# ece4416-project-v2.net
KiCad netlist of a schematic drawn in EAGLE
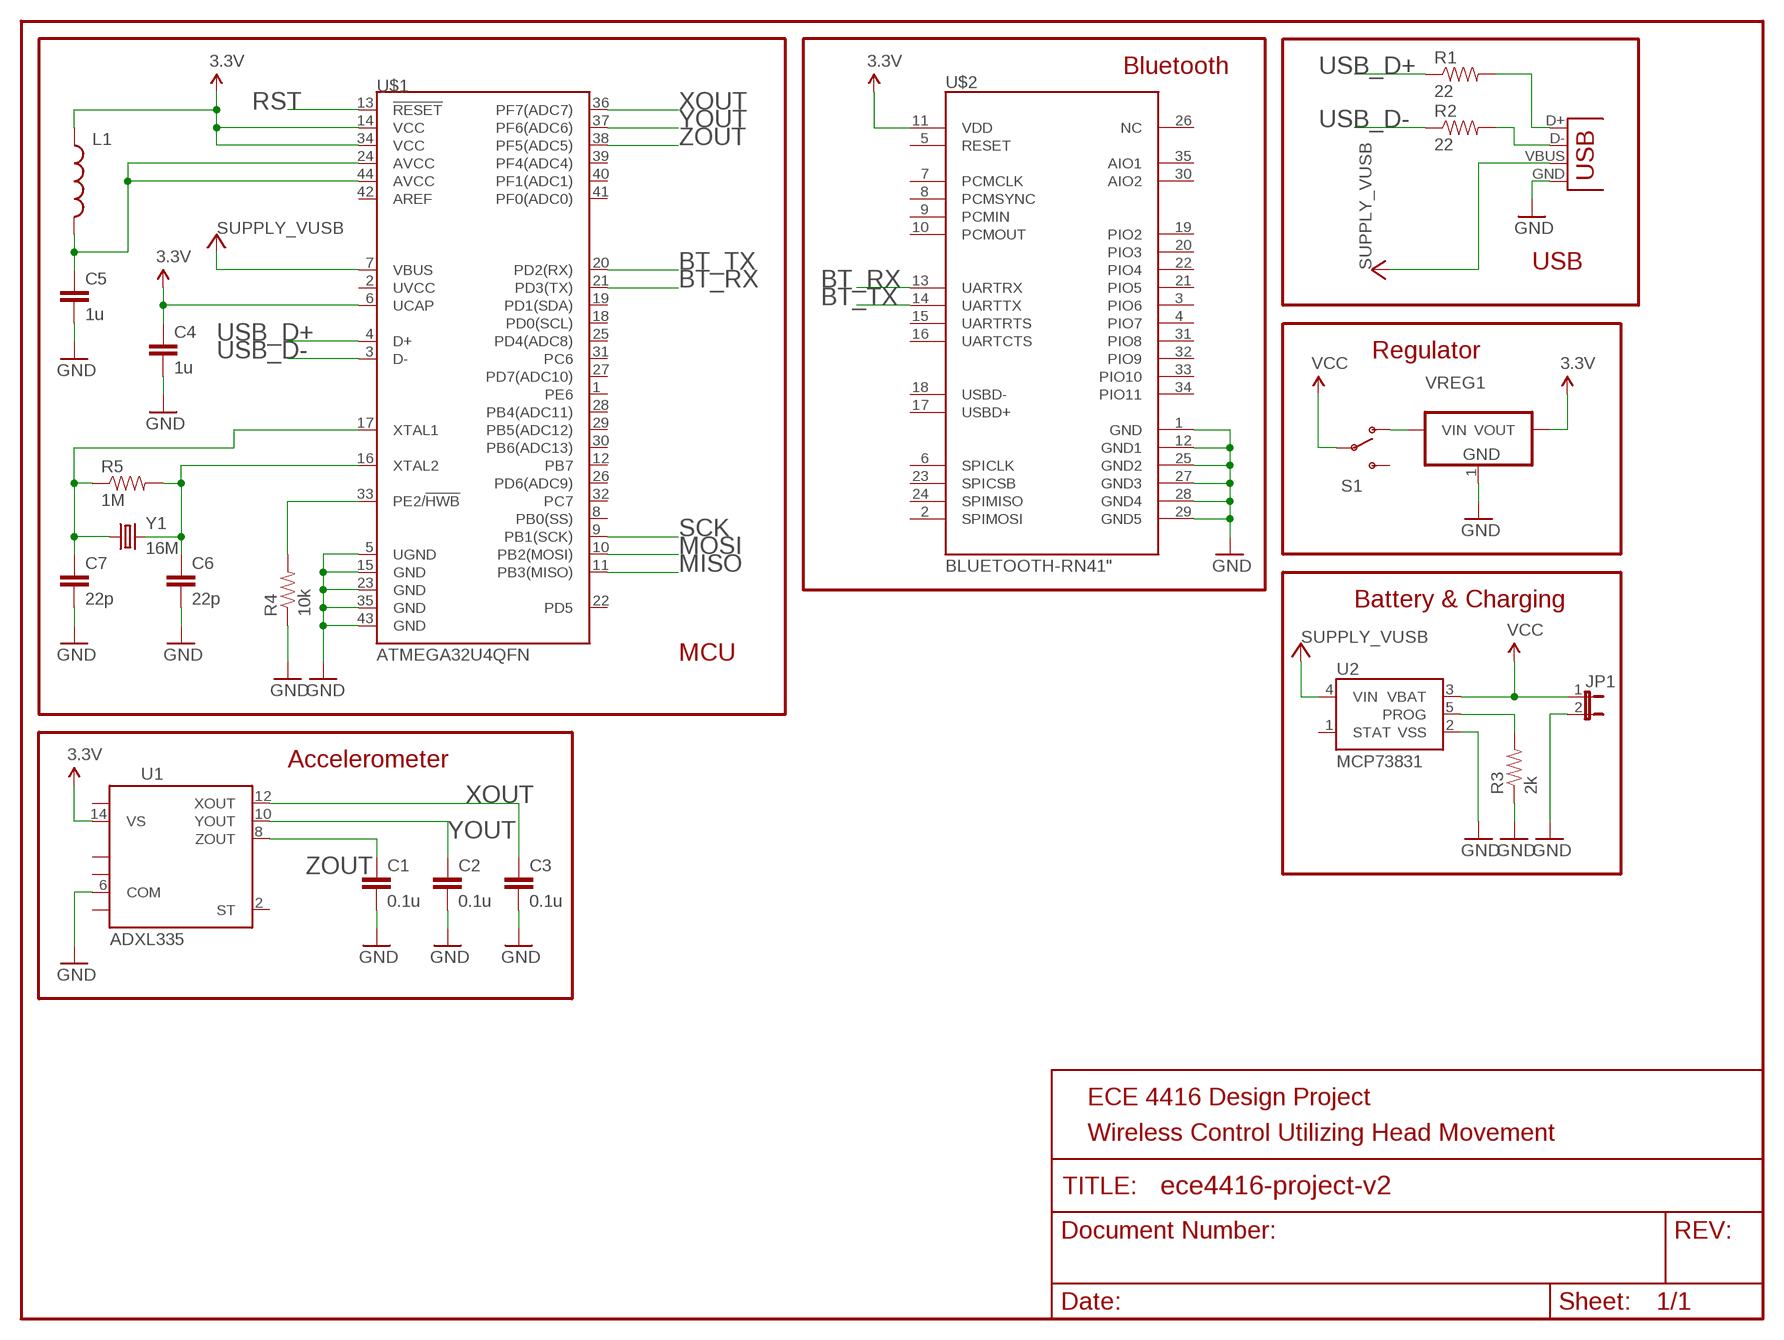
[diagram p0: schematic, sheet 1]

(export (version "E")
  (design (tool "Eeschema 10.0.6"))
  (components
    (comp (ref "C1")
      (value "0.1u")
      (footprint "eagle-import:0603-CAP")
      (libsource (lib "eagle-import") (part "CAP0603-CAP"))
    )
    (comp (ref "C2")
      (value "0.1u")
      (footprint "eagle-import:0603-CAP")
      (libsource (lib "eagle-import") (part "CAP0603-CAP"))
    )
    (comp (ref "C3")
      (value "0.1u")
      (footprint "eagle-import:0603-CAP")
      (libsource (lib "eagle-import") (part "CAP0603-CAP"))
    )
    (comp (ref "C4")
      (value "1u")
      (footprint "eagle-import:0603-CAP")
      (libsource (lib "eagle-import") (part "CAP0603-CAP"))
    )
    (comp (ref "C5")
      (value "1u")
      (footprint "eagle-import:0603-CAP")
      (libsource (lib "eagle-import") (part "CAP0603-CAP"))
    )
    (comp (ref "C6")
      (value "22p")
      (footprint "eagle-import:0603-CAP")
      (libsource (lib "eagle-import") (part "CAP0603-CAP"))
    )
    (comp (ref "C7")
      (value "22p")
      (footprint "eagle-import:0603-CAP")
      (libsource (lib "eagle-import") (part "CAP0603-CAP"))
    )
    (comp (ref "JP1")
      (value "JUMPER-2PTH")
      (footprint "eagle-import:1X02")
      (libsource (lib "eagle-import") (part "JUMPER-2PTH"))
    )
    (comp (ref "L1")
      (value "INDUCTOR0805")
      (footprint "eagle-import:0805")
      (libsource (lib "eagle-import") (part "INDUCTOR0805"))
    )
    (comp (ref "R1")
      (value "22")
      (footprint "eagle-import:0603-RES")
      (libsource (lib "eagle-import") (part "RESISTOR0603-RES"))
    )
    (comp (ref "R2")
      (value "22")
      (footprint "eagle-import:0603-RES")
      (libsource (lib "eagle-import") (part "RESISTOR0603-RES"))
    )
    (comp (ref "R3")
      (value "2k")
      (footprint "eagle-import:0603-RES")
      (libsource (lib "eagle-import") (part "RESISTOR0603-RES"))
    )
    (comp (ref "R4")
      (value "10k")
      (footprint "eagle-import:0603-RES")
      (libsource (lib "eagle-import") (part "RESISTOR0603-RES"))
    )
    (comp (ref "R5")
      (value "1M")
      (footprint "eagle-import:0603-RES")
      (libsource (lib "eagle-import") (part "RESISTOR0603-RES"))
    )
    (comp (ref "S1")
      (value "SWITCH-SPST-SMD-A")
      (footprint "eagle-import:SWITCH-SPST-SMD-A")
      (libsource (lib "eagle-import") (part "SWITCH-SPST-SMD-A"))
    )
    (comp (ref "U$1")
      (value "ATMEGA32U4QFN")
      (footprint "eagle-import:QFN-44")
      (libsource (lib "eagle-import") (part "ATMEGA32U4QFN"))
    )
    (comp (ref "U$2")
      (value "BLUETOOTH-RN41\"")
      (footprint "eagle-import:RN41")
      (libsource (lib "eagle-import") (part "BLUETOOTH-RN41{dblquote}"))
    )
    (comp (ref "U1")
      (value "ADXL335")
      (footprint "eagle-import:LFCSP-16")
      (libsource (lib "eagle-import") (part "ADXL335"))
    )
    (comp (ref "U2")
      (value "MCP73831")
      (footprint "eagle-import:SOT23-5")
      (libsource (lib "eagle-import") (part "MCP73831"))
    )
    (comp (ref "VREG1")
      (value "VREG_3PINS-SOT-223")
      (footprint "eagle-import:SOT-223")
      (libsource (lib "eagle-import") (part "VREG_3PINS-SOT-223"))
    )
    (comp (ref "X1")
      (value "USB-MICROB")
      (footprint "eagle-import:USB-MICROB")
      (libsource (lib "eagle-import") (part "USB-MICROB"))
    )
    (comp (ref "Y1")
      (value "16M")
      (footprint "eagle-import:CRYSTAL-SMD-5X3")
      (libsource (lib "eagle-import") (part "CRYSTAL5X3"))
    )
  )
  (nets
    (net (code "1") (name "/BT_RX") (class "Default")
      (node (ref "U$1") (pin "21") (pinfunction "PD3(TX)_21") (pintype "bidirectional"))
      (node (ref "U$2") (pin "13") (pinfunction "UARTRX_13") (pintype "bidirectional"))
    )
    (net (code "2") (name "/BT_TX") (class "Default")
      (node (ref "U$1") (pin "20") (pinfunction "PD2(RX)_20") (pintype "bidirectional"))
      (node (ref "U$2") (pin "14") (pinfunction "UARTTX_14") (pintype "bidirectional"))
    )
    (net (code "3") (name "/MISO") (class "Default")
      (node (ref "U$1") (pin "11") (pinfunction "PB3(MISO)_11") (pintype "bidirectional"))
    )
    (net (code "4") (name "/MOSI") (class "Default")
      (node (ref "U$1") (pin "10") (pinfunction "PB2(MOSI)_10") (pintype "bidirectional"))
    )
    (net (code "5") (name "/RST") (class "Default")
      (node (ref "U$1") (pin "13") (pinfunction "~{RESET}_13") (pintype "bidirectional"))
    )
    (net (code "6") (name "/SCK") (class "Default")
      (node (ref "U$1") (pin "9") (pinfunction "PB1(SCK)_9") (pintype "bidirectional"))
    )
    (net (code "7") (name "/USB_D+") (class "Default")
      (node (ref "R1") (pin "1") (pinfunction "1_1") (pintype "passive"))
      (node (ref "U$1") (pin "4") (pinfunction "D+_4") (pintype "bidirectional"))
    )
    (net (code "8") (name "/USB_D-") (class "Default")
      (node (ref "R2") (pin "1") (pinfunction "1_1") (pintype "passive"))
      (node (ref "U$1") (pin "3") (pinfunction "D-_3") (pintype "bidirectional"))
    )
    (net (code "9") (name "/XOUT") (class "Default")
      (node (ref "C3") (pin "1") (pinfunction "1_1") (pintype "passive"))
      (node (ref "U$1") (pin "36") (pinfunction "PF7(ADC7)_36") (pintype "bidirectional"))
      (node (ref "U1") (pin "12") (pinfunction "XOUT_12") (pintype "bidirectional"))
    )
    (net (code "10") (name "/YOUT") (class "Default")
      (node (ref "C2") (pin "1") (pinfunction "1_1") (pintype "passive"))
      (node (ref "U$1") (pin "37") (pinfunction "PF6(ADC6)_37") (pintype "bidirectional"))
      (node (ref "U1") (pin "10") (pinfunction "YOUT_10") (pintype "bidirectional"))
    )
    (net (code "11") (name "/ZOUT") (class "Default")
      (node (ref "C1") (pin "1") (pinfunction "1_1") (pintype "passive"))
      (node (ref "U$1") (pin "38") (pinfunction "PF5(ADC5)_38") (pintype "bidirectional"))
      (node (ref "U1") (pin "8") (pinfunction "ZOUT_8") (pintype "bidirectional"))
    )
    (net (code "12") (name "3.3V") (class "Default")
      (node (ref "C4") (pin "1") (pinfunction "1_1") (pintype "passive"))
      (node (ref "L1") (pin "1") (pinfunction "1_1") (pintype "passive"))
      (node (ref "U$1") (pin "14") (pinfunction "VCC_14") (pintype "bidirectional"))
      (node (ref "U$1") (pin "34") (pinfunction "VCC_34") (pintype "bidirectional"))
      (node (ref "U$1") (pin "6") (pinfunction "UCAP_6") (pintype "bidirectional"))
      (node (ref "U$2") (pin "11") (pinfunction "VDD_11") (pintype "bidirectional"))
      (node (ref "U1") (pin "14") (pinfunction "VS_14") (pintype "bidirectional"))
      (node (ref "VREG1") (pin "2") (pinfunction "VOUT_2") (pintype "bidirectional"))
    )
    (net (code "13") (name "GND") (class "Default")
      (node (ref "C1") (pin "2") (pinfunction "2_2") (pintype "passive"))
      (node (ref "C2") (pin "2") (pinfunction "2_2") (pintype "passive"))
      (node (ref "C3") (pin "2") (pinfunction "2_2") (pintype "passive"))
      (node (ref "C4") (pin "2") (pinfunction "2_2") (pintype "passive"))
      (node (ref "C5") (pin "2") (pinfunction "2_2") (pintype "passive"))
      (node (ref "C6") (pin "2") (pinfunction "2_2") (pintype "passive"))
      (node (ref "C7") (pin "2") (pinfunction "2_2") (pintype "passive"))
      (node (ref "JP1") (pin "2") (pinfunction "2_2") (pintype "passive"))
      (node (ref "R3") (pin "1") (pinfunction "1_1") (pintype "passive"))
      (node (ref "R4") (pin "1") (pinfunction "1_1") (pintype "passive"))
      (node (ref "U$1") (pin "15") (pinfunction "GND_15") (pintype "bidirectional"))
      (node (ref "U$1") (pin "23") (pinfunction "GND_23") (pintype "bidirectional"))
      (node (ref "U$1") (pin "35") (pinfunction "GND_35") (pintype "bidirectional"))
      (node (ref "U$1") (pin "43") (pinfunction "GND_43") (pintype "bidirectional"))
      (node (ref "U$1") (pin "5") (pinfunction "UGND_5") (pintype "bidirectional"))
      (node (ref "U$2") (pin "1") (pinfunction "GND_1") (pintype "bidirectional"))
      (node (ref "U$2") (pin "12") (pinfunction "GND1_12") (pintype "bidirectional"))
      (node (ref "U$2") (pin "25") (pinfunction "GND2_25") (pintype "bidirectional"))
      (node (ref "U$2") (pin "27") (pinfunction "GND3_27") (pintype "bidirectional"))
      (node (ref "U$2") (pin "28") (pinfunction "GND4_28") (pintype "bidirectional"))
      (node (ref "U$2") (pin "29") (pinfunction "GND5_29") (pintype "bidirectional"))
      (node (ref "U1") (pin "6") (pinfunction "COM_6") (pintype "bidirectional"))
      (node (ref "U2") (pin "2") (pinfunction "VSS_2") (pintype "power_in"))
      (node (ref "VREG1") (pin "1") (pinfunction "GND_1") (pintype "bidirectional"))
      (node (ref "X1") (pin "GND") (pinfunction "GND_GND") (pintype "bidirectional"))
    )
    (net (code "14") (name "Net-(C5-Pad1)") (class "Default")
      (node (ref "C5") (pin "1") (pinfunction "1_1") (pintype "passive"))
      (node (ref "L1") (pin "2") (pinfunction "2_2") (pintype "passive"))
      (node (ref "U$1") (pin "24") (pinfunction "AVCC_24") (pintype "bidirectional"))
      (node (ref "U$1") (pin "44") (pinfunction "AVCC_44") (pintype "bidirectional"))
    )
    (net (code "15") (name "Net-(R1-Pad2)") (class "Default")
      (node (ref "R1") (pin "2") (pinfunction "2_2") (pintype "passive"))
      (node (ref "X1") (pin "D+") (pinfunction "D+_D+") (pintype "bidirectional"))
    )
    (net (code "16") (name "Net-(R2-Pad2)") (class "Default")
      (node (ref "R2") (pin "2") (pinfunction "2_2") (pintype "passive"))
      (node (ref "X1") (pin "D-") (pinfunction "D-_D-") (pintype "bidirectional"))
    )
    (net (code "17") (name "Net-(S1-O)") (class "Default")
      (node (ref "S1") (pin "1") (pinfunction "O_1") (pintype "passive"))
      (node (ref "VREG1") (pin "3") (pinfunction "VIN_3") (pintype "bidirectional"))
    )
    (net (code "18") (name "Net-(U$1-PE2{slash}~{HWB})") (class "Default")
      (node (ref "R4") (pin "2") (pinfunction "2_2") (pintype "passive"))
      (node (ref "U$1") (pin "33") (pinfunction "PE2/~{HWB}_33") (pintype "bidirectional"))
    )
    (net (code "19") (name "Net-(U$1-XTAL1)") (class "Default")
      (node (ref "C7") (pin "1") (pinfunction "1_1") (pintype "passive"))
      (node (ref "R5") (pin "1") (pinfunction "1_1") (pintype "passive"))
      (node (ref "U$1") (pin "17") (pinfunction "XTAL1_17") (pintype "bidirectional"))
      (node (ref "Y1") (pin "1") (pinfunction "1_1") (pintype "passive"))
    )
    (net (code "20") (name "Net-(U$1-XTAL2)") (class "Default")
      (node (ref "C6") (pin "1") (pinfunction "1_1") (pintype "passive"))
      (node (ref "R5") (pin "2") (pinfunction "2_2") (pintype "passive"))
      (node (ref "U$1") (pin "16") (pinfunction "XTAL2_16") (pintype "bidirectional"))
      (node (ref "Y1") (pin "3") (pinfunction "2_3") (pintype "passive"))
    )
    (net (code "21") (name "Net-(U2-PROG)") (class "Default")
      (node (ref "R3") (pin "2") (pinfunction "2_2") (pintype "passive"))
      (node (ref "U2") (pin "5") (pinfunction "PROG_5") (pintype "input"))
    )
    (net (code "22") (name "SUPPLY_VUSB") (class "Default")
      (node (ref "U$1") (pin "7") (pinfunction "VBUS_7") (pintype "bidirectional"))
      (node (ref "U2") (pin "4") (pinfunction "VIN_4") (pintype "power_in"))
      (node (ref "X1") (pin "VBUS") (pinfunction "VBUS_VBUS") (pintype "bidirectional"))
    )
    (net (code "23") (name "VCC") (class "Default")
      (node (ref "JP1") (pin "1") (pinfunction "1_1") (pintype "passive"))
      (node (ref "S1") (pin "2") (pinfunction "P_2") (pintype "passive"))
      (node (ref "U2") (pin "3") (pinfunction "VBAT_3") (pintype "power_in"))
    )
    (net (code "24") (name "unconnected-(S1-S-Pad3)") (class "Default")
      (node (ref "S1") (pin "3") (pinfunction "S_3") (pintype "passive"))
    )
    (net (code "25") (name "unconnected-(U$1-AREF-Pad42)") (class "Default")
      (node (ref "U$1") (pin "42") (pinfunction "AREF_42") (pintype "bidirectional"))
    )
    (net (code "26") (name "unconnected-(U$1-PB0(SS)-Pad8)") (class "Default")
      (node (ref "U$1") (pin "8") (pinfunction "PB0(SS)_8") (pintype "bidirectional"))
    )
    (net (code "27") (name "unconnected-(U$1-PB4(ADC11)-Pad28)") (class "Default")
      (node (ref "U$1") (pin "28") (pinfunction "PB4(ADC11)_28") (pintype "bidirectional"))
    )
    (net (code "28") (name "unconnected-(U$1-PB5(ADC12)-Pad29)") (class "Default")
      (node (ref "U$1") (pin "29") (pinfunction "PB5(ADC12)_29") (pintype "bidirectional"))
    )
    (net (code "29") (name "unconnected-(U$1-PB6(ADC13)-Pad30)") (class "Default")
      (node (ref "U$1") (pin "30") (pinfunction "PB6(ADC13)_30") (pintype "bidirectional"))
    )
    (net (code "30") (name "unconnected-(U$1-PB7-Pad12)") (class "Default")
      (node (ref "U$1") (pin "12") (pinfunction "PB7_12") (pintype "bidirectional"))
    )
    (net (code "31") (name "unconnected-(U$1-PC6-Pad31)") (class "Default")
      (node (ref "U$1") (pin "31") (pinfunction "PC6_31") (pintype "bidirectional"))
    )
    (net (code "32") (name "unconnected-(U$1-PC7-Pad32)") (class "Default")
      (node (ref "U$1") (pin "32") (pinfunction "PC7_32") (pintype "bidirectional"))
    )
    (net (code "33") (name "unconnected-(U$1-PD0(SCL)-Pad18)") (class "Default")
      (node (ref "U$1") (pin "18") (pinfunction "PD0(SCL)_18") (pintype "bidirectional"))
    )
    (net (code "34") (name "unconnected-(U$1-PD1(SDA)-Pad19)") (class "Default")
      (node (ref "U$1") (pin "19") (pinfunction "PD1(SDA)_19") (pintype "bidirectional"))
    )
    (net (code "35") (name "unconnected-(U$1-PD4(ADC8)-Pad25)") (class "Default")
      (node (ref "U$1") (pin "25") (pinfunction "PD4(ADC8)_25") (pintype "bidirectional"))
    )
    (net (code "36") (name "unconnected-(U$1-PD5-Pad22)") (class "Default")
      (node (ref "U$1") (pin "22") (pinfunction "PD5_22") (pintype "bidirectional"))
    )
    (net (code "37") (name "unconnected-(U$1-PD6(ADC9)-Pad26)") (class "Default")
      (node (ref "U$1") (pin "26") (pinfunction "PD6(ADC9)_26") (pintype "bidirectional"))
    )
    (net (code "38") (name "unconnected-(U$1-PD7(ADC10)-Pad27)") (class "Default")
      (node (ref "U$1") (pin "27") (pinfunction "PD7(ADC10)_27") (pintype "bidirectional"))
    )
    (net (code "39") (name "unconnected-(U$1-PE6-Pad1)") (class "Default")
      (node (ref "U$1") (pin "1") (pinfunction "PE6_1") (pintype "bidirectional"))
    )
    (net (code "40") (name "unconnected-(U$1-PF0(ADC0)-Pad41)") (class "Default")
      (node (ref "U$1") (pin "41") (pinfunction "PF0(ADC0)_41") (pintype "bidirectional"))
    )
    (net (code "41") (name "unconnected-(U$1-PF1(ADC1)-Pad40)") (class "Default")
      (node (ref "U$1") (pin "40") (pinfunction "PF1(ADC1)_40") (pintype "bidirectional"))
    )
    (net (code "42") (name "unconnected-(U$1-PF4(ADC4)-Pad39)") (class "Default")
      (node (ref "U$1") (pin "39") (pinfunction "PF4(ADC4)_39") (pintype "bidirectional"))
    )
    (net (code "43") (name "unconnected-(U$1-UVCC-Pad2)") (class "Default")
      (node (ref "U$1") (pin "2") (pinfunction "UVCC_2") (pintype "bidirectional"))
    )
    (net (code "44") (name "unconnected-(U$2-AIO1-Pad35)") (class "Default")
      (node (ref "U$2") (pin "35") (pinfunction "AIO1_35") (pintype "bidirectional"))
    )
    (net (code "45") (name "unconnected-(U$2-AIO2-Pad30)") (class "Default")
      (node (ref "U$2") (pin "30") (pinfunction "AIO2_30") (pintype "bidirectional"))
    )
    (net (code "46") (name "unconnected-(U$2-NC-Pad26)") (class "Default")
      (node (ref "U$2") (pin "26") (pinfunction "NC_26") (pintype "bidirectional"))
    )
    (net (code "47") (name "unconnected-(U$2-PCMCLK-Pad7)") (class "Default")
      (node (ref "U$2") (pin "7") (pinfunction "PCMCLK_7") (pintype "bidirectional"))
    )
    (net (code "48") (name "unconnected-(U$2-PCMIN-Pad9)") (class "Default")
      (node (ref "U$2") (pin "9") (pinfunction "PCMIN_9") (pintype "bidirectional"))
    )
    (net (code "49") (name "unconnected-(U$2-PCMOUT-Pad10)") (class "Default")
      (node (ref "U$2") (pin "10") (pinfunction "PCMOUT_10") (pintype "bidirectional"))
    )
    (net (code "50") (name "unconnected-(U$2-PCMSYNC-Pad8)") (class "Default")
      (node (ref "U$2") (pin "8") (pinfunction "PCMSYNC_8") (pintype "bidirectional"))
    )
    (net (code "51") (name "unconnected-(U$2-PIO2-Pad19)") (class "Default")
      (node (ref "U$2") (pin "19") (pinfunction "PIO2_19") (pintype "bidirectional"))
    )
    (net (code "52") (name "unconnected-(U$2-PIO3-Pad20)") (class "Default")
      (node (ref "U$2") (pin "20") (pinfunction "PIO3_20") (pintype "bidirectional"))
    )
    (net (code "53") (name "unconnected-(U$2-PIO4-Pad22)") (class "Default")
      (node (ref "U$2") (pin "22") (pinfunction "PIO4_22") (pintype "bidirectional"))
    )
    (net (code "54") (name "unconnected-(U$2-PIO5-Pad21)") (class "Default")
      (node (ref "U$2") (pin "21") (pinfunction "PIO5_21") (pintype "bidirectional"))
    )
    (net (code "55") (name "unconnected-(U$2-PIO6-Pad3)") (class "Default")
      (node (ref "U$2") (pin "3") (pinfunction "PIO6_3") (pintype "bidirectional"))
    )
    (net (code "56") (name "unconnected-(U$2-PIO7-Pad4)") (class "Default")
      (node (ref "U$2") (pin "4") (pinfunction "PIO7_4") (pintype "bidirectional"))
    )
    (net (code "57") (name "unconnected-(U$2-PIO8-Pad31)") (class "Default")
      (node (ref "U$2") (pin "31") (pinfunction "PIO8_31") (pintype "bidirectional"))
    )
    (net (code "58") (name "unconnected-(U$2-PIO9-Pad32)") (class "Default")
      (node (ref "U$2") (pin "32") (pinfunction "PIO9_32") (pintype "bidirectional"))
    )
    (net (code "59") (name "unconnected-(U$2-PIO10-Pad33)") (class "Default")
      (node (ref "U$2") (pin "33") (pinfunction "PIO10_33") (pintype "bidirectional"))
    )
    (net (code "60") (name "unconnected-(U$2-PIO11-Pad34)") (class "Default")
      (node (ref "U$2") (pin "34") (pinfunction "PIO11_34") (pintype "bidirectional"))
    )
    (net (code "61") (name "unconnected-(U$2-RESET-Pad5)") (class "Default")
      (node (ref "U$2") (pin "5") (pinfunction "RESET_5") (pintype "bidirectional"))
    )
    (net (code "62") (name "unconnected-(U$2-SPICLK-Pad6)") (class "Default")
      (node (ref "U$2") (pin "6") (pinfunction "SPICLK_6") (pintype "bidirectional"))
    )
    (net (code "63") (name "unconnected-(U$2-SPICSB-Pad23)") (class "Default")
      (node (ref "U$2") (pin "23") (pinfunction "SPICSB_23") (pintype "bidirectional"))
    )
    (net (code "64") (name "unconnected-(U$2-SPIMISO-Pad24)") (class "Default")
      (node (ref "U$2") (pin "24") (pinfunction "SPIMISO_24") (pintype "bidirectional"))
    )
    (net (code "65") (name "unconnected-(U$2-SPIMOSI-Pad2)") (class "Default")
      (node (ref "U$2") (pin "2") (pinfunction "SPIMOSI_2") (pintype "bidirectional"))
    )
    (net (code "66") (name "unconnected-(U$2-UARTCTS-Pad16)") (class "Default")
      (node (ref "U$2") (pin "16") (pinfunction "UARTCTS_16") (pintype "bidirectional"))
    )
    (net (code "67") (name "unconnected-(U$2-UARTRTS-Pad15)") (class "Default")
      (node (ref "U$2") (pin "15") (pinfunction "UARTRTS_15") (pintype "bidirectional"))
    )
    (net (code "68") (name "unconnected-(U$2-USBD+-Pad17)") (class "Default")
      (node (ref "U$2") (pin "17") (pinfunction "USBD+_17") (pintype "bidirectional"))
    )
    (net (code "69") (name "unconnected-(U$2-USBD--Pad18)") (class "Default")
      (node (ref "U$2") (pin "18") (pinfunction "USBD-_18") (pintype "bidirectional"))
    )
    (net (code "70") (name "unconnected-(U1-COM-Pad3)") (class "Default")
      (node (ref "U1") (pin "3") (pinfunction "COM_3") (pintype "bidirectional"))
    )
    (net (code "71") (name "unconnected-(U1-COM-Pad5)") (class "Default")
      (node (ref "U1") (pin "5") (pinfunction "COM_5") (pintype "bidirectional"))
    )
    (net (code "72") (name "unconnected-(U1-COM-Pad7)") (class "Default")
      (node (ref "U1") (pin "7") (pinfunction "COM_7") (pintype "bidirectional"))
    )
    (net (code "73") (name "unconnected-(U1-ST-Pad2)") (class "Default")
      (node (ref "U1") (pin "2") (pinfunction "ST_2") (pintype "bidirectional"))
    )
    (net (code "74") (name "unconnected-(U1-VS-Pad15)") (class "Default")
      (node (ref "U1") (pin "15") (pinfunction "VS_15") (pintype "bidirectional"))
    )
    (net (code "75") (name "unconnected-(U2-STAT-Pad1)") (class "Default")
      (node (ref "U2") (pin "1") (pinfunction "STAT_1") (pintype "output"))
    )
  )
)
